# PNPController.net
KiCad netlist of a schematic drawn in EAGLE
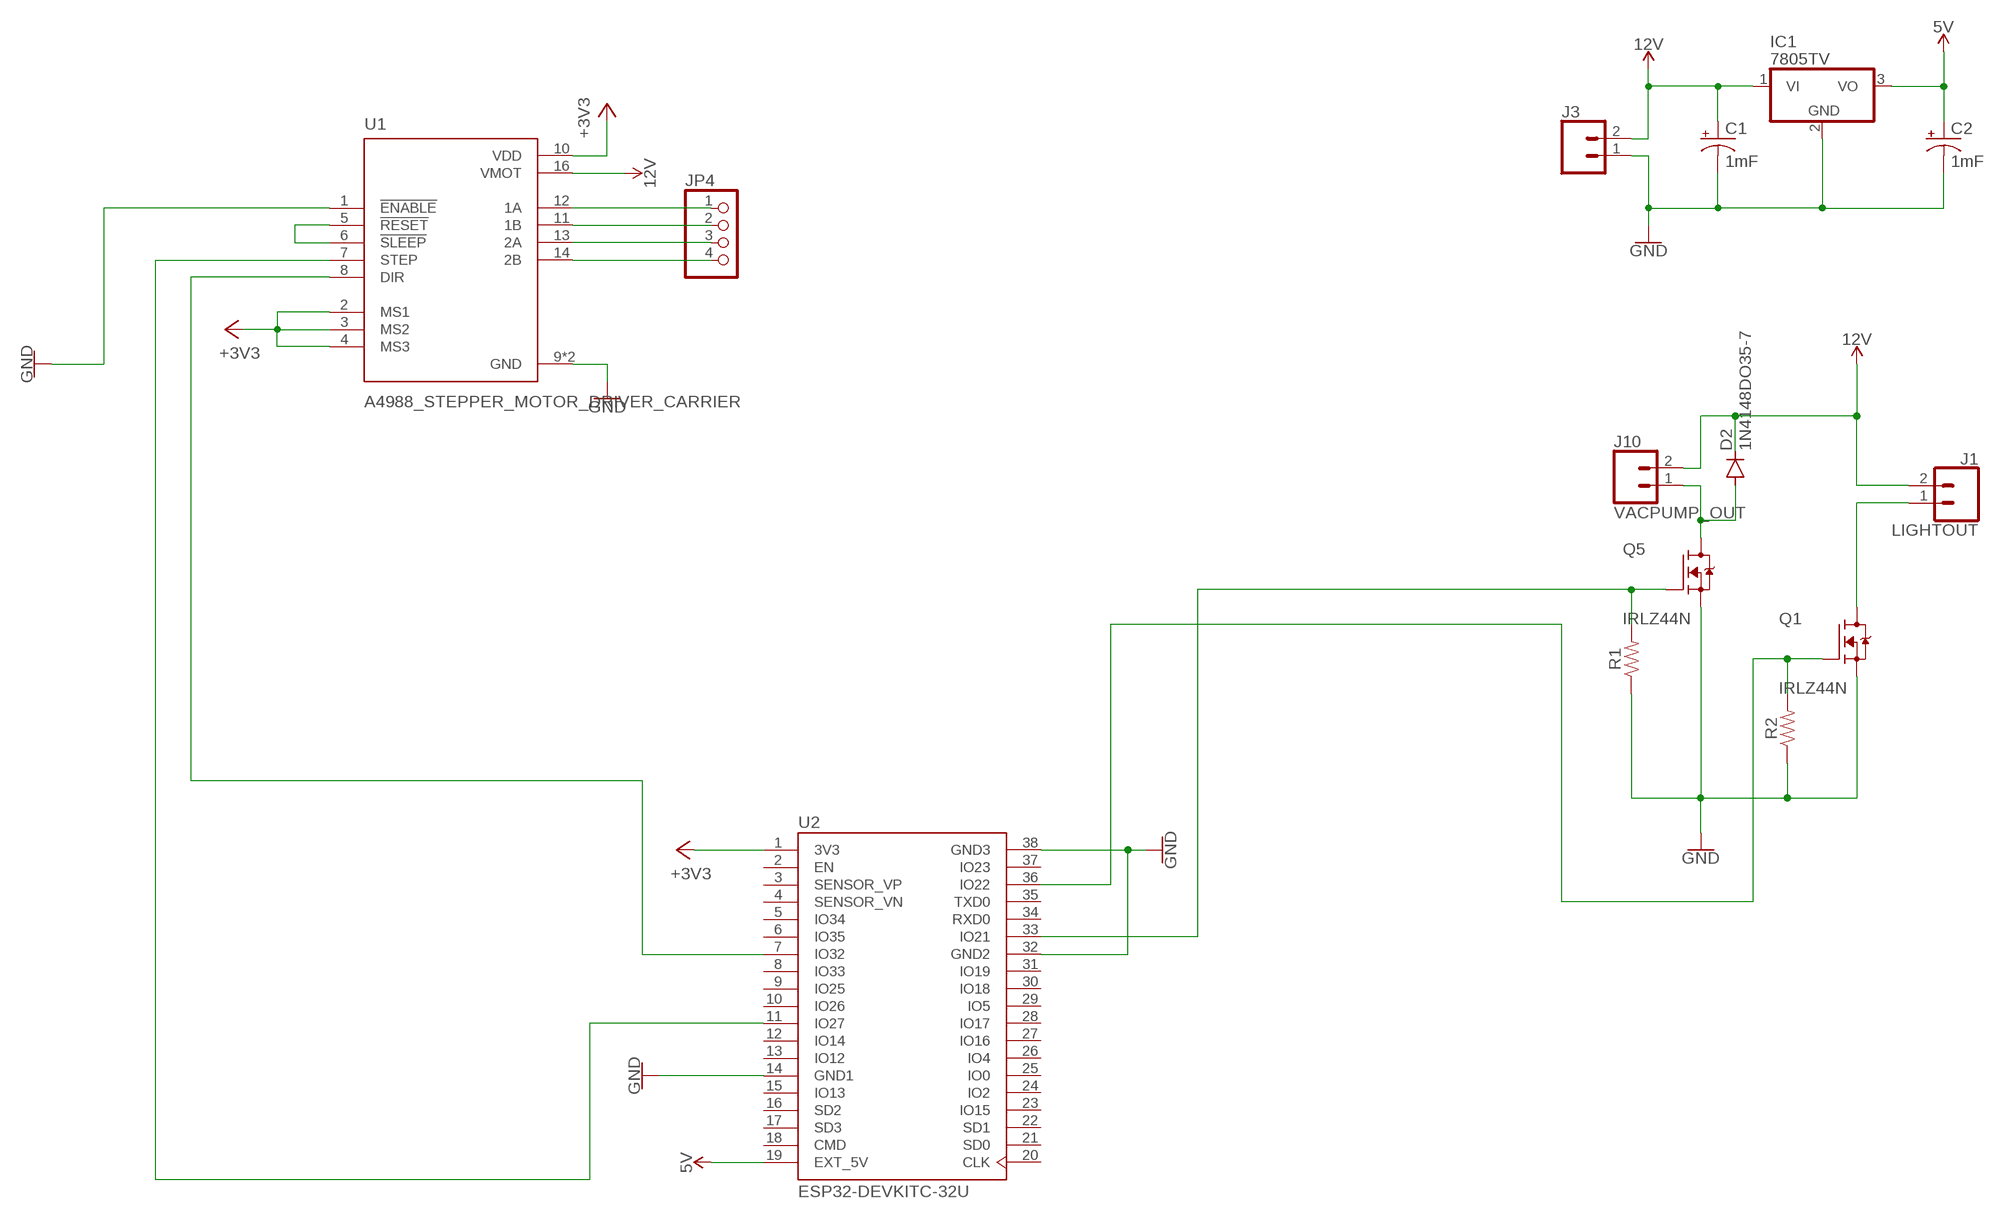
[diagram p0: schematic, sheet 1]

(export (version "E")
  (design (tool "Eeschema 10.0.6"))
  (components
    (comp (ref "C1")
      (value "1mF")
      (footprint "eagle-import:CPOL-RADIAL-5MM-10MM")
      (libsource (lib "eagle-import") (part "1000UF-RADIAL-5MM-25V-20%"))
    )
    (comp (ref "C2")
      (value "1mF")
      (footprint "eagle-import:CPOL-RADIAL-5MM-10MM")
      (libsource (lib "eagle-import") (part "1000UF-RADIAL-5MM-25V-20%"))
    )
    (comp (ref "D2")
      (value "1N4148DO35-7")
      (footprint "eagle-import:DO35-7")
      (libsource (lib "eagle-import") (part "1N4148DO35-7"))
    )
    (comp (ref "IC1")
      (value "7805TV")
      (footprint "eagle-import:TO220V")
      (libsource (lib "eagle-import") (part "78TV05"))
    )
    (comp (ref "J1")
      (value "LIGHTOUT")
      (footprint "eagle-import:SCREWTERMINAL-3.5MM-2")
      (libsource (lib "eagle-import") (part "CONN_023.5MM"))
    )
    (comp (ref "J3")
      (value "CONN_025MM")
      (footprint "eagle-import:SCREWTERMINAL-5MM-2")
      (libsource (lib "eagle-import") (part "CONN_025MM"))
    )
    (comp (ref "J10")
      (value "VACPUMP_OUT")
      (footprint "eagle-import:SCREWTERMINAL-3.5MM-2")
      (libsource (lib "eagle-import") (part "CONN_023.5MM"))
    )
    (comp (ref "JP4")
      (value "PINHD-1X4")
      (footprint "eagle-import:1X04")
      (libsource (lib "eagle-import") (part "PINHD-1X4"))
    )
    (comp (ref "Q1")
      (value "IRLZ44N")
      (footprint "eagle-import:TO254P1054X469X1930-3")
      (fields (field (name "MF") "Infineon / IR"))
      (libsource (lib "eagle-import") (part "IRLZ44N"))
    )
    (comp (ref "Q5")
      (value "IRLZ44N")
      (footprint "eagle-import:TO254P1054X469X1930-3")
      (fields (field (name "MF") "Infineon / IR"))
      (libsource (lib "eagle-import") (part "IRLZ44N"))
    )
    (comp (ref "R1")
      (value "RESISTORAXIAL-0.3")
      (footprint "eagle-import:AXIAL-0.3")
      (libsource (lib "eagle-import") (part "RESISTORAXIAL-0.3"))
    )
    (comp (ref "R2")
      (value "RESISTORAXIAL-0.3")
      (footprint "eagle-import:AXIAL-0.3")
      (libsource (lib "eagle-import") (part "RESISTORAXIAL-0.3"))
    )
    (comp (ref "U1")
      (value "A4988_STEPPER_MOTOR_DRIVER_CARRIER")
      (footprint "eagle-import:MODULE_A4988_STEPPER_MOTOR_DRIVER_CARRIER")
      (fields (field (name "MF") "Pololu") (field (name "MP") "A4988 STEPPER MOTOR DRIVER CARRIER"))
      (libsource (lib "eagle-import") (part "A4988_STEPPER_MOTOR_DRIVER_CARRIER"))
    )
    (comp (ref "U2")
      (value "ESP32-DEVKITC-32U")
      (footprint "eagle-import:MODULE_ESP32-DEVKITC-32U")
      (fields (field (name "MF") "Espressif Systems"))
      (libsource (lib "eagle-import") (part "ESP32-DEVKITC-32U"))
    )
  )
  (nets
    (net (code "1") (name "+3V3") (class "Default")
      (node (ref "U1") (pin "10") (pinfunction "VDD_10") (pintype "power_in"))
      (node (ref "U1") (pin "2") (pinfunction "MS1_2") (pintype "input"))
      (node (ref "U1") (pin "3") (pinfunction "MS2_3") (pintype "input"))
      (node (ref "U1") (pin "4") (pinfunction "MS3_4") (pintype "input"))
      (node (ref "U2") (pin "1") (pinfunction "3V3_1") (pintype "power_in"))
    )
    (net (code "2") (name "5V") (class "Default")
      (node (ref "C2") (pin "+") (pinfunction "+_+") (pintype "passive"))
      (node (ref "IC1") (pin "3") (pinfunction "VO_3") (pintype "passive"))
      (node (ref "U2") (pin "19") (pinfunction "EXT_5V_19") (pintype "power_in"))
    )
    (net (code "3") (name "12V") (class "Default")
      (node (ref "C1") (pin "+") (pinfunction "+_+") (pintype "passive"))
      (node (ref "D2") (pin "C") (pinfunction "C_C") (pintype "passive"))
      (node (ref "IC1") (pin "1") (pinfunction "VI_1") (pintype "input"))
      (node (ref "J1") (pin "2") (pinfunction "2_2") (pintype "passive"))
      (node (ref "J10") (pin "2") (pinfunction "2_2") (pintype "passive"))
      (node (ref "J3") (pin "2") (pinfunction "2_2") (pintype "passive"))
      (node (ref "U1") (pin "16") (pinfunction "VMOT_16") (pintype "power_in"))
    )
    (net (code "4") (name "GND") (class "Default")
      (node (ref "C1") (pin "-") (pinfunction "-_-") (pintype "passive"))
      (node (ref "C2") (pin "-") (pinfunction "-_-") (pintype "passive"))
      (node (ref "IC1") (pin "2") (pinfunction "GND_2") (pintype "passive"))
      (node (ref "J3") (pin "1") (pinfunction "1_1") (pintype "passive"))
      (node (ref "Q1") (pin "3") (pinfunction "S_3") (pintype "passive"))
      (node (ref "Q5") (pin "3") (pinfunction "S_3") (pintype "passive"))
      (node (ref "R1") (pin "P$1") (pinfunction "1_P$1") (pintype "passive"))
      (node (ref "R2") (pin "P$1") (pinfunction "1_P$1") (pintype "passive"))
      (node (ref "U1") (pin "1") (pinfunction "~{ENABLE}_1") (pintype "input"))
      (node (ref "U1") (pin "15") (pinfunction "GND_15") (pintype "power_in"))
      (node (ref "U1") (pin "9") (pinfunction "GND_9") (pintype "power_in"))
      (node (ref "U2") (pin "14") (pinfunction "GND1_14") (pintype "power_in"))
      (node (ref "U2") (pin "32") (pinfunction "GND2_32") (pintype "power_in"))
      (node (ref "U2") (pin "38") (pinfunction "GND3_38") (pintype "power_in"))
    )
    (net (code "5") (name "Net-(Q1-D)") (class "Default")
      (node (ref "J1") (pin "1") (pinfunction "1_1") (pintype "passive"))
      (node (ref "Q1") (pin "2") (pinfunction "D_2") (pintype "passive"))
    )
    (net (code "6") (name "Net-(Q1-G)") (class "Default")
      (node (ref "Q1") (pin "1") (pinfunction "G_1") (pintype "passive"))
      (node (ref "R2") (pin "P$2") (pinfunction "2_P$2") (pintype "passive"))
      (node (ref "U2") (pin "36") (pinfunction "IO22_36") (pintype "bidirectional"))
    )
    (net (code "7") (name "Net-(Q5-D)") (class "Default")
      (node (ref "D2") (pin "A") (pinfunction "A_A") (pintype "passive"))
      (node (ref "J10") (pin "1") (pinfunction "1_1") (pintype "passive"))
      (node (ref "Q5") (pin "2") (pinfunction "D_2") (pintype "passive"))
    )
    (net (code "8") (name "Net-(Q5-G)") (class "Default")
      (node (ref "Q5") (pin "1") (pinfunction "G_1") (pintype "passive"))
      (node (ref "R1") (pin "P$2") (pinfunction "2_P$2") (pintype "passive"))
      (node (ref "U2") (pin "33") (pinfunction "IO21_33") (pintype "bidirectional"))
    )
    (net (code "9") (name "Net-(U1-1A)") (class "Default")
      (node (ref "JP4") (pin "1") (pinfunction "1_1") (pintype "passive"))
      (node (ref "U1") (pin "12") (pinfunction "1A_12") (pintype "output"))
    )
    (net (code "10") (name "Net-(U1-1B)") (class "Default")
      (node (ref "JP4") (pin "2") (pinfunction "2_2") (pintype "passive"))
      (node (ref "U1") (pin "11") (pinfunction "1B_11") (pintype "output"))
    )
    (net (code "11") (name "Net-(U1-2A)") (class "Default")
      (node (ref "JP4") (pin "3") (pinfunction "3_3") (pintype "passive"))
      (node (ref "U1") (pin "13") (pinfunction "2A_13") (pintype "output"))
    )
    (net (code "12") (name "Net-(U1-2B)") (class "Default")
      (node (ref "JP4") (pin "4") (pinfunction "4_4") (pintype "passive"))
      (node (ref "U1") (pin "14") (pinfunction "2B_14") (pintype "output"))
    )
    (net (code "13") (name "Net-(U1-DIR)") (class "Default")
      (node (ref "U1") (pin "8") (pinfunction "DIR_8") (pintype "input"))
      (node (ref "U2") (pin "7") (pinfunction "IO32_7") (pintype "bidirectional"))
    )
    (net (code "14") (name "Net-(U1-STEP)") (class "Default")
      (node (ref "U1") (pin "7") (pinfunction "STEP_7") (pintype "input"))
      (node (ref "U2") (pin "11") (pinfunction "IO27_11") (pintype "bidirectional"))
    )
    (net (code "15") (name "Net-(U1-~{RESET})") (class "Default")
      (node (ref "U1") (pin "5") (pinfunction "~{RESET}_5") (pintype "input"))
      (node (ref "U1") (pin "6") (pinfunction "~{SLEEP}_6") (pintype "input"))
    )
    (net (code "16") (name "unconnected-(U2-CLK-Pad20)") (class "Default")
      (node (ref "U2") (pin "20") (pinfunction "CLK_20") (pintype "input"))
    )
    (net (code "17") (name "unconnected-(U2-CMD-Pad18)") (class "Default")
      (node (ref "U2") (pin "18") (pinfunction "CMD_18") (pintype "bidirectional"))
    )
    (net (code "18") (name "unconnected-(U2-EN-Pad2)") (class "Default")
      (node (ref "U2") (pin "2") (pinfunction "EN_2") (pintype "input"))
    )
    (net (code "19") (name "unconnected-(U2-IO0-Pad25)") (class "Default")
      (node (ref "U2") (pin "25") (pinfunction "IO0_25") (pintype "bidirectional"))
    )
    (net (code "20") (name "unconnected-(U2-IO2-Pad24)") (class "Default")
      (node (ref "U2") (pin "24") (pinfunction "IO2_24") (pintype "bidirectional"))
    )
    (net (code "21") (name "unconnected-(U2-IO4-Pad26)") (class "Default")
      (node (ref "U2") (pin "26") (pinfunction "IO4_26") (pintype "bidirectional"))
    )
    (net (code "22") (name "unconnected-(U2-IO5-Pad29)") (class "Default")
      (node (ref "U2") (pin "29") (pinfunction "IO5_29") (pintype "bidirectional"))
    )
    (net (code "23") (name "unconnected-(U2-IO12-Pad13)") (class "Default")
      (node (ref "U2") (pin "13") (pinfunction "IO12_13") (pintype "bidirectional"))
    )
    (net (code "24") (name "unconnected-(U2-IO13-Pad15)") (class "Default")
      (node (ref "U2") (pin "15") (pinfunction "IO13_15") (pintype "bidirectional"))
    )
    (net (code "25") (name "unconnected-(U2-IO14-Pad12)") (class "Default")
      (node (ref "U2") (pin "12") (pinfunction "IO14_12") (pintype "bidirectional"))
    )
    (net (code "26") (name "unconnected-(U2-IO15-Pad23)") (class "Default")
      (node (ref "U2") (pin "23") (pinfunction "IO15_23") (pintype "bidirectional"))
    )
    (net (code "27") (name "unconnected-(U2-IO16-Pad27)") (class "Default")
      (node (ref "U2") (pin "27") (pinfunction "IO16_27") (pintype "bidirectional"))
    )
    (net (code "28") (name "unconnected-(U2-IO17-Pad28)") (class "Default")
      (node (ref "U2") (pin "28") (pinfunction "IO17_28") (pintype "bidirectional"))
    )
    (net (code "29") (name "unconnected-(U2-IO18-Pad30)") (class "Default")
      (node (ref "U2") (pin "30") (pinfunction "IO18_30") (pintype "bidirectional"))
    )
    (net (code "30") (name "unconnected-(U2-IO19-Pad31)") (class "Default")
      (node (ref "U2") (pin "31") (pinfunction "IO19_31") (pintype "bidirectional"))
    )
    (net (code "31") (name "unconnected-(U2-IO23-Pad37)") (class "Default")
      (node (ref "U2") (pin "37") (pinfunction "IO23_37") (pintype "bidirectional"))
    )
    (net (code "32") (name "unconnected-(U2-IO25-Pad9)") (class "Default")
      (node (ref "U2") (pin "9") (pinfunction "IO25_9") (pintype "bidirectional"))
    )
    (net (code "33") (name "unconnected-(U2-IO26-Pad10)") (class "Default")
      (node (ref "U2") (pin "10") (pinfunction "IO26_10") (pintype "bidirectional"))
    )
    (net (code "34") (name "unconnected-(U2-IO33-Pad8)") (class "Default")
      (node (ref "U2") (pin "8") (pinfunction "IO33_8") (pintype "bidirectional"))
    )
    (net (code "35") (name "unconnected-(U2-IO34-Pad5)") (class "Default")
      (node (ref "U2") (pin "5") (pinfunction "IO34_5") (pintype "bidirectional"))
    )
    (net (code "36") (name "unconnected-(U2-IO35-Pad6)") (class "Default")
      (node (ref "U2") (pin "6") (pinfunction "IO35_6") (pintype "bidirectional"))
    )
    (net (code "37") (name "unconnected-(U2-RXD0-Pad34)") (class "Default")
      (node (ref "U2") (pin "34") (pinfunction "RXD0_34") (pintype "input"))
    )
    (net (code "38") (name "unconnected-(U2-SD0-Pad21)") (class "Default")
      (node (ref "U2") (pin "21") (pinfunction "SD0_21") (pintype "bidirectional"))
    )
    (net (code "39") (name "unconnected-(U2-SD1-Pad22)") (class "Default")
      (node (ref "U2") (pin "22") (pinfunction "SD1_22") (pintype "bidirectional"))
    )
    (net (code "40") (name "unconnected-(U2-SD2-Pad16)") (class "Default")
      (node (ref "U2") (pin "16") (pinfunction "SD2_16") (pintype "bidirectional"))
    )
    (net (code "41") (name "unconnected-(U2-SD3-Pad17)") (class "Default")
      (node (ref "U2") (pin "17") (pinfunction "SD3_17") (pintype "bidirectional"))
    )
    (net (code "42") (name "unconnected-(U2-SENSOR_VN-Pad4)") (class "Default")
      (node (ref "U2") (pin "4") (pinfunction "SENSOR_VN_4") (pintype "input"))
    )
    (net (code "43") (name "unconnected-(U2-SENSOR_VP-Pad3)") (class "Default")
      (node (ref "U2") (pin "3") (pinfunction "SENSOR_VP_3") (pintype "input"))
    )
    (net (code "44") (name "unconnected-(U2-TXD0-Pad35)") (class "Default")
      (node (ref "U2") (pin "35") (pinfunction "TXD0_35") (pintype "output"))
    )
  )
)
